# PIPCB.net
KiCad netlist of a schematic drawn in EAGLE
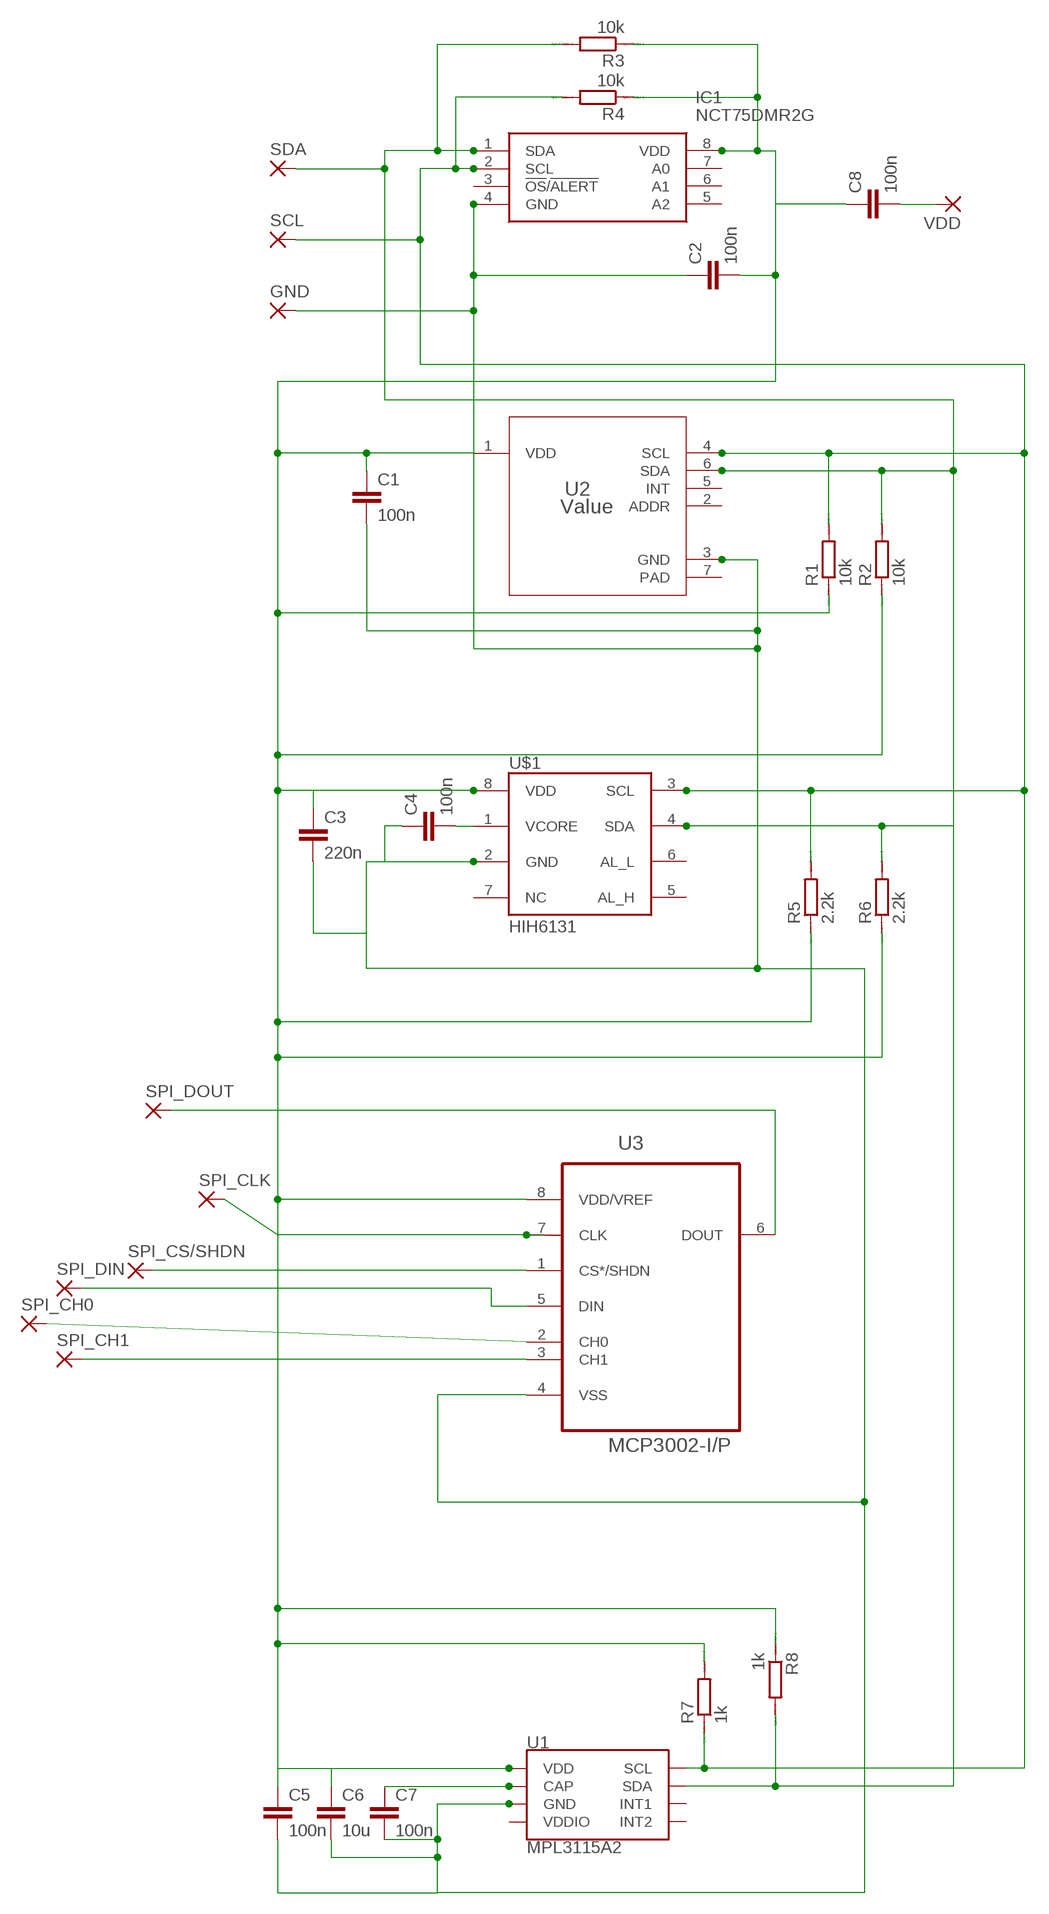
[diagram p0: schematic, sheet 1]

(export (version "E")
  (design (tool "Eeschema 10.0.6"))
  (components
    (comp (ref "C1")
      (value "100n")
      (footprint "eagle-import:C2.5-3")
      (libsource (lib "eagle-import") (part "C2,5-3"))
    )
    (comp (ref "C2")
      (value "100n")
      (footprint "eagle-import:C2.5-3")
      (libsource (lib "eagle-import") (part "C2,5-3"))
    )
    (comp (ref "C3")
      (value "220n")
      (footprint "eagle-import:C2.5-3")
      (libsource (lib "eagle-import") (part "C2,5-3"))
    )
    (comp (ref "C4")
      (value "100n")
      (footprint "eagle-import:C2.5-3")
      (libsource (lib "eagle-import") (part "C2,5-3"))
    )
    (comp (ref "C5")
      (value "100n")
      (footprint "eagle-import:C2.5-3")
      (libsource (lib "eagle-import") (part "C2,5-3"))
    )
    (comp (ref "C6")
      (value "10u")
      (footprint "eagle-import:C2.5-3")
      (libsource (lib "eagle-import") (part "C2,5-3"))
    )
    (comp (ref "C7")
      (value "100n")
      (footprint "eagle-import:C2.5-3")
      (libsource (lib "eagle-import") (part "C2,5-3"))
    )
    (comp (ref "C8")
      (value "100n")
      (footprint "eagle-import:C2.5-3")
      (libsource (lib "eagle-import") (part "C2,5-3"))
    )
    (comp (ref "GND")
      (value "2,54/0,8")
      (footprint "eagle-import:2,54_0,8")
      (libsource (lib "eagle-import") (part "2,54/0,8"))
    )
    (comp (ref "IC1")
      (value "NCT75DMR2G")
      (footprint "eagle-import:SOP65P490X110-8N")
      (fields (field (name "RS_PART_NUMBER") "8064942"))
      (libsource (lib "eagle-import") (part "NCT75DMR2G"))
    )
    (comp (ref "R1")
      (value "10k")
      (footprint "eagle-import:0207_10")
      (libsource (lib "eagle-import") (part "R0207/10"))
    )
    (comp (ref "R2")
      (value "10k")
      (footprint "eagle-import:0207_10")
      (libsource (lib "eagle-import") (part "R0207/10"))
    )
    (comp (ref "R3")
      (value "10k")
      (footprint "eagle-import:0207_10")
      (libsource (lib "eagle-import") (part "R0207/10"))
    )
    (comp (ref "R4")
      (value "10k")
      (footprint "eagle-import:0207_10")
      (libsource (lib "eagle-import") (part "R0207/10"))
    )
    (comp (ref "R5")
      (value "2.2k")
      (footprint "eagle-import:0207_10")
      (libsource (lib "eagle-import") (part "R0207/10"))
    )
    (comp (ref "R6")
      (value "2.2k")
      (footprint "eagle-import:0207_10")
      (libsource (lib "eagle-import") (part "R0207/10"))
    )
    (comp (ref "R7")
      (value "1k")
      (footprint "eagle-import:0207_10")
      (libsource (lib "eagle-import") (part "R0207/10"))
    )
    (comp (ref "R8")
      (value "1k")
      (footprint "eagle-import:0207_10")
      (libsource (lib "eagle-import") (part "R0207/10"))
    )
    (comp (ref "SCL")
      (value "2,54/0,8")
      (footprint "eagle-import:2,54_0,8")
      (libsource (lib "eagle-import") (part "2,54/0,8"))
    )
    (comp (ref "SDA")
      (value "2,54/0,8")
      (footprint "eagle-import:2,54_0,8")
      (libsource (lib "eagle-import") (part "2,54/0,8"))
    )
    (comp (ref "SPI_CH0")
      (value "2,54/0,8")
      (footprint "eagle-import:2,54_0,8")
      (libsource (lib "eagle-import") (part "2,54/0,8"))
    )
    (comp (ref "SPI_CH1")
      (value "2,54/0,8")
      (footprint "eagle-import:2,54_0,8")
      (libsource (lib "eagle-import") (part "2,54/0,8"))
    )
    (comp (ref "SPI_CLK")
      (value "2,54/0,8")
      (footprint "eagle-import:2,54_0,8")
      (libsource (lib "eagle-import") (part "2,54/0,8"))
    )
    (comp (ref "SPI_CS/SHDN")
      (value "2,54/0,8")
      (footprint "eagle-import:2,54_0,8")
      (libsource (lib "eagle-import") (part "2,54/0,8"))
    )
    (comp (ref "SPI_DIN")
      (value "2,54/0,8")
      (footprint "eagle-import:2,54_0,8")
      (libsource (lib "eagle-import") (part "2,54/0,8"))
    )
    (comp (ref "SPI_DOUT")
      (value "2,54/0,8")
      (footprint "eagle-import:2,54_0,8")
      (libsource (lib "eagle-import") (part "2,54/0,8"))
    )
    (comp (ref "U$1")
      (value "HIH6131")
      (footprint "eagle-import:SOIC8")
      (libsource (lib "eagle-import") (part "HIH6131"))
    )
    (comp (ref "U1")
      (value "MPL3115A2")
      (footprint "eagle-import:LGA-8-5X3")
      (libsource (lib "eagle-import") (part "MPL3115A2"))
    )
    (comp (ref "U2")
      (value "Value")
      (footprint "eagle-import:DNP0006A")
      (fields (field (name "MANUFACTURER") "Texas Instruments") (field (name "PARTNUMBER") "OPT3001DNP"))
      (libsource (lib "eagle-import") (part "OPT3001DNPR"))
    )
    (comp (ref "U3")
      (value "MCP3002-I/P")
      (footprint "eagle-import:DIP254P762X533-8")
      (libsource (lib "eagle-import") (part "MCP3002-I/P"))
    )
    (comp (ref "VDD")
      (value "2,54/0,8")
      (footprint "eagle-import:2,54_0,8")
      (libsource (lib "eagle-import") (part "2,54/0,8"))
    )
  )
  (nets
    (net (code "1") (name "/VDDIO") (class "Default")
      (node (ref "U1") (pin "4") (pinfunction "VDDIO_4") (pintype "power_in"))
    )
    (net (code "2") (name "Net-(GND-P)") (class "Default")
      (node (ref "C1") (pin "2") (pinfunction "2_2") (pintype "passive"))
      (node (ref "C2") (pin "1") (pinfunction "1_1") (pintype "passive"))
      (node (ref "C3") (pin "2") (pinfunction "2_2") (pintype "passive"))
      (node (ref "C4") (pin "1") (pinfunction "1_1") (pintype "passive"))
      (node (ref "C5") (pin "2") (pinfunction "2_2") (pintype "passive"))
      (node (ref "C6") (pin "2") (pinfunction "2_2") (pintype "passive"))
      (node (ref "C7") (pin "2") (pinfunction "2_2") (pintype "passive"))
      (node (ref "GND") (pin "1") (pinfunction "P_1") (pintype "passive"))
      (node (ref "IC1") (pin "4") (pinfunction "GND_4") (pintype "power_in"))
      (node (ref "U$1") (pin "2") (pinfunction "GND_2") (pintype "bidirectional"))
      (node (ref "U1") (pin "3") (pinfunction "GND_3") (pintype "power_in"))
      (node (ref "U2") (pin "3") (pinfunction "GND_3") (pintype "power_in"))
      (node (ref "U3") (pin "4") (pinfunction "VSS_4") (pintype "passive"))
    )
    (net (code "3") (name "Net-(IC1-SCL)") (class "Default")
      (node (ref "IC1") (pin "2") (pinfunction "SCL_2") (pintype "bidirectional"))
      (node (ref "R1") (pin "2") (pinfunction "2_2") (pintype "passive"))
      (node (ref "R4") (pin "2") (pinfunction "2_2") (pintype "passive"))
      (node (ref "R5") (pin "2") (pinfunction "2_2") (pintype "passive"))
      (node (ref "R7") (pin "1") (pinfunction "1_1") (pintype "passive"))
      (node (ref "SCL") (pin "1") (pinfunction "P_1") (pintype "passive"))
      (node (ref "U$1") (pin "3") (pinfunction "SCL_3") (pintype "bidirectional"))
      (node (ref "U1") (pin "8") (pinfunction "SCL_8") (pintype "bidirectional"))
      (node (ref "U2") (pin "4") (pinfunction "SCL_4") (pintype "input"))
    )
    (net (code "4") (name "Net-(IC1-SDA)") (class "Default")
      (node (ref "IC1") (pin "1") (pinfunction "SDA_1") (pintype "bidirectional"))
      (node (ref "R2") (pin "2") (pinfunction "2_2") (pintype "passive"))
      (node (ref "R3") (pin "2") (pinfunction "2_2") (pintype "passive"))
      (node (ref "R6") (pin "2") (pinfunction "2_2") (pintype "passive"))
      (node (ref "R8") (pin "2") (pinfunction "2_2") (pintype "passive"))
      (node (ref "SDA") (pin "1") (pinfunction "P_1") (pintype "passive"))
      (node (ref "U$1") (pin "4") (pinfunction "SDA_4") (pintype "bidirectional"))
      (node (ref "U1") (pin "7") (pinfunction "SDA_7") (pintype "bidirectional"))
      (node (ref "U2") (pin "6") (pinfunction "SDA_6") (pintype "input"))
    )
    (net (code "5") (name "Net-(IC1-VDD)") (class "Default")
      (node (ref "C1") (pin "1") (pinfunction "1_1") (pintype "passive"))
      (node (ref "C2") (pin "2") (pinfunction "2_2") (pintype "passive"))
      (node (ref "C3") (pin "1") (pinfunction "1_1") (pintype "passive"))
      (node (ref "C5") (pin "1") (pinfunction "1_1") (pintype "passive"))
      (node (ref "C6") (pin "1") (pinfunction "1_1") (pintype "passive"))
      (node (ref "C8") (pin "1") (pinfunction "1_1") (pintype "passive"))
      (node (ref "IC1") (pin "8") (pinfunction "VDD_8") (pintype "power_in"))
      (node (ref "R1") (pin "1") (pinfunction "1_1") (pintype "passive"))
      (node (ref "R2") (pin "1") (pinfunction "1_1") (pintype "passive"))
      (node (ref "R3") (pin "1") (pinfunction "1_1") (pintype "passive"))
      (node (ref "R4") (pin "1") (pinfunction "1_1") (pintype "passive"))
      (node (ref "R5") (pin "1") (pinfunction "1_1") (pintype "passive"))
      (node (ref "R6") (pin "1") (pinfunction "1_1") (pintype "passive"))
      (node (ref "R7") (pin "2") (pinfunction "2_2") (pintype "passive"))
      (node (ref "R8") (pin "1") (pinfunction "1_1") (pintype "passive"))
      (node (ref "U$1") (pin "8") (pinfunction "VDD_8") (pintype "bidirectional"))
      (node (ref "U1") (pin "1") (pinfunction "VDD_1") (pintype "power_in"))
      (node (ref "U2") (pin "1") (pinfunction "VDD_1") (pintype "power_in"))
      (node (ref "U3") (pin "8") (pinfunction "VDD/VREF_8") (pintype "power_in"))
    )
    (net (code "6") (name "Net-(SPI_CH0-P)") (class "Default")
      (node (ref "SPI_CH0") (pin "1") (pinfunction "P_1") (pintype "passive"))
      (node (ref "U3") (pin "2") (pinfunction "CH0_2") (pintype "input"))
    )
    (net (code "7") (name "Net-(SPI_CH1-P)") (class "Default")
      (node (ref "SPI_CH1") (pin "1") (pinfunction "P_1") (pintype "passive"))
      (node (ref "U3") (pin "3") (pinfunction "CH1_3") (pintype "input"))
    )
    (net (code "8") (name "Net-(SPI_CLK-P)") (class "Default")
      (node (ref "SPI_CLK") (pin "1") (pinfunction "P_1") (pintype "passive"))
      (node (ref "U3") (pin "7") (pinfunction "CLK_7") (pintype "input"))
    )
    (net (code "9") (name "Net-(SPI_CS/SHDN-P)") (class "Default")
      (node (ref "SPI_CS/SHDN") (pin "1") (pinfunction "P_1") (pintype "passive"))
      (node (ref "U3") (pin "1") (pinfunction "CS*/SHDN_1") (pintype "input"))
    )
    (net (code "10") (name "Net-(SPI_DIN-P)") (class "Default")
      (node (ref "SPI_DIN") (pin "1") (pinfunction "P_1") (pintype "passive"))
      (node (ref "U3") (pin "5") (pinfunction "DIN_5") (pintype "input"))
    )
    (net (code "11") (name "Net-(SPI_DOUT-P)") (class "Default")
      (node (ref "SPI_DOUT") (pin "1") (pinfunction "P_1") (pintype "passive"))
      (node (ref "U3") (pin "6") (pinfunction "DOUT_6") (pintype "output"))
    )
    (net (code "12") (name "Net-(U$1-VCORE)") (class "Default")
      (node (ref "C4") (pin "2") (pinfunction "2_2") (pintype "passive"))
      (node (ref "U$1") (pin "1") (pinfunction "VCORE_1") (pintype "bidirectional"))
    )
    (net (code "13") (name "Net-(U1-CAP)") (class "Default")
      (node (ref "C7") (pin "1") (pinfunction "1_1") (pintype "passive"))
      (node (ref "U1") (pin "2") (pinfunction "CAP_2") (pintype "power_in"))
    )
    (net (code "14") (name "Net-(VDD-P)") (class "Default")
      (node (ref "C8") (pin "2") (pinfunction "2_2") (pintype "passive"))
      (node (ref "VDD") (pin "1") (pinfunction "P_1") (pintype "passive"))
    )
    (net (code "15") (name "unconnected-(IC1-A0-Pad7)") (class "Default")
      (node (ref "IC1") (pin "7") (pinfunction "A0_7") (pintype "bidirectional"))
    )
    (net (code "16") (name "unconnected-(IC1-A1-Pad6)") (class "Default")
      (node (ref "IC1") (pin "6") (pinfunction "A1_6") (pintype "bidirectional"))
    )
    (net (code "17") (name "unconnected-(IC1-A2-Pad5)") (class "Default")
      (node (ref "IC1") (pin "5") (pinfunction "A2_5") (pintype "bidirectional"))
    )
    (net (code "18") (name "unconnected-(IC1-~{OS}{slash}~{ALERT}-Pad3)") (class "Default")
      (node (ref "IC1") (pin "3") (pinfunction "~{OS}/~{ALERT}_3") (pintype "bidirectional"))
    )
    (net (code "19") (name "unconnected-(U$1-AL_H-Pad5)") (class "Default")
      (node (ref "U$1") (pin "5") (pinfunction "AL_H_5") (pintype "bidirectional"))
    )
    (net (code "20") (name "unconnected-(U$1-AL_L-Pad6)") (class "Default")
      (node (ref "U$1") (pin "6") (pinfunction "AL_L_6") (pintype "bidirectional"))
    )
    (net (code "21") (name "unconnected-(U$1-NC-Pad7)") (class "Default")
      (node (ref "U$1") (pin "7") (pinfunction "NC_7") (pintype "bidirectional"))
    )
    (net (code "22") (name "unconnected-(U1-INT1-Pad6)") (class "Default")
      (node (ref "U1") (pin "6") (pinfunction "INT1_6") (pintype "output"))
    )
    (net (code "23") (name "unconnected-(U1-INT2-Pad5)") (class "Default")
      (node (ref "U1") (pin "5") (pinfunction "INT2_5") (pintype "output"))
    )
    (net (code "24") (name "unconnected-(U2-ADDR-Pad2)") (class "Default")
      (node (ref "U2") (pin "2") (pinfunction "ADDR_2") (pintype "input"))
    )
    (net (code "25") (name "unconnected-(U2-INT-Pad5)") (class "Default")
      (node (ref "U2") (pin "5") (pinfunction "INT_5") (pintype "output"))
    )
    (net (code "26") (name "unconnected-(U2-PAD-Pad7)") (class "Default")
      (node (ref "U2") (pin "7") (pinfunction "PAD_7") (pintype "passive"))
    )
  )
)
